# scr_gate.net
KiCad netlist of a schematic drawn in EAGLE
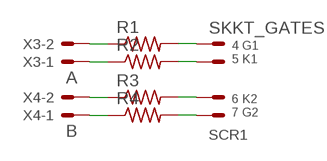
[diagram p0: schematic, sheet 1]

(export (version "E")
  (design (tool "Eeschema 10.0.6"))
  (components
    (comp (ref "R1")
      (value "R-US_M0805")
      (footprint "eagle-import:M0805")
      (libsource (lib "eagle-import") (part "R-US_M0805"))
    )
    (comp (ref "R2")
      (value "R-US_M0805")
      (footprint "eagle-import:M0805")
      (libsource (lib "eagle-import") (part "R-US_M0805"))
    )
    (comp (ref "R3")
      (value "R-US_M0805")
      (footprint "eagle-import:M0805")
      (libsource (lib "eagle-import") (part "R-US_M0805"))
    )
    (comp (ref "R4")
      (value "R-US_M0805")
      (footprint "eagle-import:M0805")
      (libsource (lib "eagle-import") (part "R-US_M0805"))
    )
    (comp (ref "SCR1")
      (value "SKKT_GATES")
      (footprint "eagle-import:SKKT_GATES")
      (libsource (lib "eagle-import") (part "SKKT_GATES"))
    )
    (comp (ref "X3")
      (value "A")
      (footprint "eagle-import:22-23-2021")
      (fields (field (name "MF") "MOLEX") (field (name "MPN") "22-23-2021"))
      (libsource (lib "eagle-import") (part "22-23-2021"))
    )
    (comp (ref "X4")
      (value "B")
      (footprint "eagle-import:22-23-2021")
      (fields (field (name "MF") "MOLEX") (field (name "MPN") "22-23-2021"))
      (libsource (lib "eagle-import") (part "22-23-2021"))
    )
  )
  (nets
    (net (code "1") (name "Net-(R1-Pad2)") (class "Default")
      (node (ref "R1") (pin "2") (pinfunction "2_2") (pintype "passive"))
      (node (ref "SCR1") (pin "P$1") (pinfunction "1_P$1") (pintype "passive"))
      (node (ref "SCR1") (pin "P$5") (pinfunction "1_P$5") (pintype "passive"))
    )
    (net (code "2") (name "Net-(R2-Pad2)") (class "Default")
      (node (ref "R2") (pin "2") (pinfunction "2_2") (pintype "passive"))
      (node (ref "SCR1") (pin "P$2") (pinfunction "2_P$2") (pintype "passive"))
      (node (ref "SCR1") (pin "P$6") (pinfunction "2_P$6") (pintype "passive"))
    )
    (net (code "3") (name "Net-(R3-Pad2)") (class "Default")
      (node (ref "R3") (pin "2") (pinfunction "2_2") (pintype "passive"))
      (node (ref "SCR1") (pin "P$3") (pinfunction "3_P$3") (pintype "passive"))
      (node (ref "SCR1") (pin "P$7") (pinfunction "3_P$7") (pintype "passive"))
    )
    (net (code "4") (name "Net-(R4-Pad2)") (class "Default")
      (node (ref "R4") (pin "2") (pinfunction "2_2") (pintype "passive"))
      (node (ref "SCR1") (pin "P$4") (pinfunction "4_P$4") (pintype "passive"))
      (node (ref "SCR1") (pin "P$8") (pinfunction "4_P$8") (pintype "passive"))
    )
    (net (code "5") (name "Net-(X3A-S)") (class "Default")
      (node (ref "R2") (pin "1") (pinfunction "1_1") (pintype "passive"))
      (node (ref "X3") (pin "1") (pinfunction "S_1") (pintype "passive"))
    )
    (net (code "6") (name "Net-(X3B-S)") (class "Default")
      (node (ref "R1") (pin "1") (pinfunction "1_1") (pintype "passive"))
      (node (ref "X3") (pin "2") (pinfunction "S_2") (pintype "passive"))
    )
    (net (code "7") (name "Net-(X4A-S)") (class "Default")
      (node (ref "R4") (pin "1") (pinfunction "1_1") (pintype "passive"))
      (node (ref "X4") (pin "1") (pinfunction "S_1") (pintype "passive"))
    )
    (net (code "8") (name "Net-(X4B-S)") (class "Default")
      (node (ref "R3") (pin "1") (pinfunction "1_1") (pintype "passive"))
      (node (ref "X4") (pin "2") (pinfunction "S_2") (pintype "passive"))
    )
  )
)
